# USB-C-UPDI.net
KiCad netlist of a schematic drawn in EAGLE
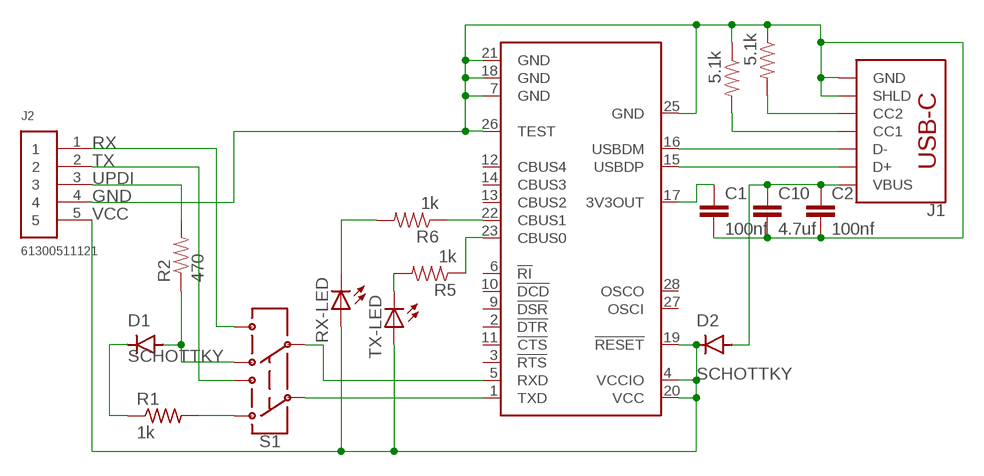
[diagram p0: schematic, sheet 1]

(export (version "E")
  (design (tool "Eeschema 10.0.6"))
  (components
    (comp (ref "C1")
      (value "100nf")
      (footprint "eagle-import:1206")
      (libsource (lib "eagle-import") (part "CAP1206"))
    )
    (comp (ref "C2")
      (value "100nf")
      (footprint "eagle-import:1206")
      (libsource (lib "eagle-import") (part "CAP1206"))
    )
    (comp (ref "C10")
      (value "4.7uf")
      (footprint "eagle-import:1206")
      (libsource (lib "eagle-import") (part "CAP1206"))
    )
    (comp (ref "D1")
      (value "SCHOTTKY")
      (footprint "eagle-import:MINI-SMA")
      (libsource (lib "eagle-import") (part "DIODE_SCHOTTKY_CDBM1100-G"))
    )
    (comp (ref "D2")
      (value "SCHOTTKY")
      (footprint "eagle-import:MINI-SMA")
      (libsource (lib "eagle-import") (part "DIODE_SCHOTTKY_CDBM1100-G"))
    )
    (comp (ref "IC1")
      (value "FT232RL")
      (footprint "eagle-import:SSOP28")
      (libsource (lib "eagle-import") (part "FT232RL"))
    )
    (comp (ref "J1")
      (value "USB_C_4-LAYER_PADS")
      (footprint "eagle-import:USB-C-16P_4LAYER-PADS")
      (libsource (lib "eagle-import") (part "USB_C_4-LAYER_PADS"))
    )
    (comp (ref "J2")
      (value "61300511121")
      (footprint "eagle-import:61300511121")
      (fields
        (field (name "DIGI_KEY_PART_NUMBER") "732-5318-ND")
        (field (name "MANUFACTURER") "Wurth Electronics Inc.")
        (field (name "CREATED_BY") "PCBLayout.com")
      )
      (libsource (lib "eagle-import") (part "61300511121"))
    )
    (comp (ref "R1")
      (value "1k")
      (footprint "eagle-import:R1206FAB")
      (libsource (lib "eagle-import") (part "R1206FAB"))
    )
    (comp (ref "R2")
      (value "470")
      (footprint "eagle-import:1206")
      (libsource (lib "eagle-import") (part "RESISTOR1206"))
    )
    (comp (ref "R5")
      (value "1k")
      (footprint "eagle-import:1206")
      (libsource (lib "eagle-import") (part "RESISTOR1206"))
    )
    (comp (ref "R6")
      (value "1k")
      (footprint "eagle-import:1206")
      (libsource (lib "eagle-import") (part "RESISTOR1206"))
    )
    (comp (ref "R9")
      (value "5.1k")
      (footprint "eagle-import:1206")
      (libsource (lib "eagle-import") (part "RESISTOR1206"))
    )
    (comp (ref "R10")
      (value "5.1k")
      (footprint "eagle-import:1206")
      (libsource (lib "eagle-import") (part "RESISTOR1206"))
    )
    (comp (ref "RX-LED")
      (value "LED")
      (footprint "eagle-import:LED1206")
      (libsource (lib "eagle-import") (part "LED"))
    )
    (comp (ref "S1")
      (value "SWITCH-DPDT-SMD-AYZ0202")
      (footprint "eagle-import:SWITCH_DPDT_SMD_AYZ0202")
      (libsource (lib "eagle-import") (part "SWITCH-DPDT-SMD-AYZ0202"))
    )
    (comp (ref "TX-LED")
      (value "LED")
      (footprint "eagle-import:LED1206")
      (libsource (lib "eagle-import") (part "LED"))
    )
  )
  (nets
    (net (code "1") (name "/GND") (class "Default")
      (node (ref "C1") (pin "2") (pinfunction "2_2") (pintype "passive"))
      (node (ref "C10") (pin "2") (pinfunction "2_2") (pintype "passive"))
      (node (ref "C2") (pin "2") (pinfunction "2_2") (pintype "passive"))
      (node (ref "IC1") (pin "18") (pinfunction "GND_18") (pintype "power_in"))
      (node (ref "IC1") (pin "21") (pinfunction "GND_21") (pintype "power_in"))
      (node (ref "IC1") (pin "25") (pinfunction "GND_25") (pintype "power_in"))
      (node (ref "IC1") (pin "26") (pinfunction "TEST_26") (pintype "input"))
      (node (ref "IC1") (pin "7") (pinfunction "GND_7") (pintype "power_in"))
      (node (ref "J1") (pin "GND") (pinfunction "GND_GND") (pintype "bidirectional"))
      (node (ref "J1") (pin "GND2") (pinfunction "GND_GND2") (pintype "bidirectional"))
      (node (ref "J1") (pin "SHLD1") (pinfunction "SHLD_SHLD1") (pintype "bidirectional"))
      (node (ref "J1") (pin "SHLD2") (pinfunction "SHLD_SHLD2") (pintype "bidirectional"))
      (node (ref "J1") (pin "SHLD3") (pinfunction "SHLD_SHLD3") (pintype "bidirectional"))
      (node (ref "J1") (pin "SHLD4") (pinfunction "SHLD_SHLD4") (pintype "bidirectional"))
      (node (ref "J2") (pin "4") (pinfunction "4_4") (pintype "passive"))
      (node (ref "R10") (pin "1") (pinfunction "1_1") (pintype "passive"))
      (node (ref "R9") (pin "1") (pinfunction "1_1") (pintype "passive"))
    )
    (net (code "2") (name "/RX") (class "Default")
      (node (ref "J2") (pin "1") (pinfunction "1_1") (pintype "passive"))
      (node (ref "S1") (pin "4") (pinfunction "4_4") (pintype "bidirectional"))
    )
    (net (code "3") (name "/TX") (class "Default")
      (node (ref "J2") (pin "2") (pinfunction "2_2") (pintype "passive"))
      (node (ref "S1") (pin "1") (pinfunction "1_1") (pintype "bidirectional"))
    )
    (net (code "4") (name "/UPDI") (class "Default")
      (node (ref "J2") (pin "3") (pinfunction "3_3") (pintype "passive"))
      (node (ref "R2") (pin "2") (pinfunction "2_2") (pintype "passive"))
    )
    (net (code "5") (name "/VCC") (class "Default")
      (node (ref "D2") (pin "KATHODE") (pinfunction "KATHODE_KATHODE") (pintype "bidirectional"))
      (node (ref "IC1") (pin "19") (pinfunction "~{RESET}_19") (pintype "input"))
      (node (ref "IC1") (pin "20") (pinfunction "VCC_20") (pintype "power_in"))
      (node (ref "IC1") (pin "4") (pinfunction "VCCIO_4") (pintype "power_in"))
      (node (ref "J2") (pin "5") (pinfunction "5_5") (pintype "passive"))
      (node (ref "RX-LED") (pin "1") (pinfunction "A_1") (pintype "passive"))
      (node (ref "TX-LED") (pin "1") (pinfunction "A_1") (pintype "passive"))
    )
    (net (code "6") (name "Net-(C10-Pad1)") (class "Default")
      (node (ref "C10") (pin "1") (pinfunction "1_1") (pintype "passive"))
      (node (ref "C2") (pin "1") (pinfunction "1_1") (pintype "passive"))
      (node (ref "D2") (pin "ANODE") (pinfunction "ANODE_ANODE") (pintype "bidirectional"))
      (node (ref "J1") (pin "VBUS1") (pinfunction "VBUS_VBUS1") (pintype "bidirectional"))
      (node (ref "J1") (pin "VBUS2") (pinfunction "VBUS_VBUS2") (pintype "bidirectional"))
    )
    (net (code "7") (name "Net-(D1-PadANODE)") (class "Default")
      (node (ref "D1") (pin "ANODE") (pinfunction "ANODE_ANODE") (pintype "bidirectional"))
      (node (ref "R2") (pin "1") (pinfunction "1_1") (pintype "passive"))
      (node (ref "S1") (pin "6") (pinfunction "6_6") (pintype "bidirectional"))
    )
    (net (code "8") (name "Net-(D1-PadKATHODE)") (class "Default")
      (node (ref "D1") (pin "KATHODE") (pinfunction "KATHODE_KATHODE") (pintype "bidirectional"))
      (node (ref "R1") (pin "1") (pinfunction "1_1") (pintype "passive"))
    )
    (net (code "9") (name "Net-(IC1-3V3OUT)") (class "Default")
      (node (ref "C1") (pin "1") (pinfunction "1_1") (pintype "passive"))
      (node (ref "IC1") (pin "17") (pinfunction "3V3OUT_17") (pintype "output"))
    )
    (net (code "10") (name "Net-(IC1-CBUS0)") (class "Default")
      (node (ref "IC1") (pin "23") (pinfunction "CBUS0_23") (pintype "bidirectional"))
      (node (ref "R5") (pin "1") (pinfunction "1_1") (pintype "passive"))
    )
    (net (code "11") (name "Net-(IC1-CBUS1)") (class "Default")
      (node (ref "IC1") (pin "22") (pinfunction "CBUS1_22") (pintype "bidirectional"))
      (node (ref "R6") (pin "1") (pinfunction "1_1") (pintype "passive"))
    )
    (net (code "12") (name "Net-(IC1-RXD)") (class "Default")
      (node (ref "IC1") (pin "5") (pinfunction "RXD_5") (pintype "input"))
      (node (ref "S1") (pin "5") (pinfunction "5_5") (pintype "bidirectional"))
    )
    (net (code "13") (name "Net-(IC1-TXD)") (class "Default")
      (node (ref "IC1") (pin "1") (pinfunction "TXD_1") (pintype "output"))
      (node (ref "S1") (pin "2") (pinfunction "2_2") (pintype "bidirectional"))
    )
    (net (code "14") (name "Net-(IC1-USBDM)") (class "Default")
      (node (ref "IC1") (pin "16") (pinfunction "USBDM_16") (pintype "bidirectional"))
      (node (ref "J1") (pin "A7") (pinfunction "D-_A7") (pintype "bidirectional"))
      (node (ref "J1") (pin "B7") (pinfunction "D-_B7") (pintype "bidirectional"))
    )
    (net (code "15") (name "Net-(IC1-USBDP)") (class "Default")
      (node (ref "IC1") (pin "15") (pinfunction "USBDP_15") (pintype "bidirectional"))
      (node (ref "J1") (pin "A6") (pinfunction "D+_A6") (pintype "bidirectional"))
      (node (ref "J1") (pin "B6") (pinfunction "D+_B6") (pintype "bidirectional"))
    )
    (net (code "16") (name "Net-(J1-CC1)") (class "Default")
      (node (ref "J1") (pin "A5") (pinfunction "CC1_A5") (pintype "bidirectional"))
      (node (ref "R9") (pin "2") (pinfunction "2_2") (pintype "passive"))
    )
    (net (code "17") (name "Net-(J1-CC2)") (class "Default")
      (node (ref "J1") (pin "B5") (pinfunction "CC2_B5") (pintype "bidirectional"))
      (node (ref "R10") (pin "2") (pinfunction "2_2") (pintype "passive"))
    )
    (net (code "18") (name "Net-(R1-Pad2)") (class "Default")
      (node (ref "R1") (pin "2") (pinfunction "2_2") (pintype "passive"))
      (node (ref "S1") (pin "3") (pinfunction "3_3") (pintype "bidirectional"))
    )
    (net (code "19") (name "Net-(RX-LED-C)") (class "Default")
      (node (ref "R6") (pin "2") (pinfunction "2_2") (pintype "passive"))
      (node (ref "RX-LED") (pin "2") (pinfunction "C_2") (pintype "passive"))
    )
    (net (code "20") (name "Net-(TX-LED-C)") (class "Default")
      (node (ref "R5") (pin "2") (pinfunction "2_2") (pintype "passive"))
      (node (ref "TX-LED") (pin "2") (pinfunction "C_2") (pintype "passive"))
    )
    (net (code "21") (name "unconnected-(IC1-CBUS2-Pad13)") (class "Default")
      (node (ref "IC1") (pin "13") (pinfunction "CBUS2_13") (pintype "bidirectional"))
    )
    (net (code "22") (name "unconnected-(IC1-CBUS3-Pad14)") (class "Default")
      (node (ref "IC1") (pin "14") (pinfunction "CBUS3_14") (pintype "bidirectional"))
    )
    (net (code "23") (name "unconnected-(IC1-CBUS4-Pad12)") (class "Default")
      (node (ref "IC1") (pin "12") (pinfunction "CBUS4_12") (pintype "bidirectional"))
    )
    (net (code "24") (name "unconnected-(IC1-OSCI-Pad27)") (class "Default")
      (node (ref "IC1") (pin "27") (pinfunction "OSCI_27") (pintype "input"))
    )
    (net (code "25") (name "unconnected-(IC1-OSCO-Pad28)") (class "Default")
      (node (ref "IC1") (pin "28") (pinfunction "OSCO_28") (pintype "output"))
    )
    (net (code "26") (name "unconnected-(IC1-~{CTS}-Pad11)") (class "Default")
      (node (ref "IC1") (pin "11") (pinfunction "~{CTS}_11") (pintype "input"))
    )
    (net (code "27") (name "unconnected-(IC1-~{DCD}-Pad10)") (class "Default")
      (node (ref "IC1") (pin "10") (pinfunction "~{DCD}_10") (pintype "input"))
    )
    (net (code "28") (name "unconnected-(IC1-~{DSR}-Pad9)") (class "Default")
      (node (ref "IC1") (pin "9") (pinfunction "~{DSR}_9") (pintype "input"))
    )
    (net (code "29") (name "unconnected-(IC1-~{DTR}-Pad2)") (class "Default")
      (node (ref "IC1") (pin "2") (pinfunction "~{DTR}_2") (pintype "output"))
    )
    (net (code "30") (name "unconnected-(IC1-~{RI}-Pad6)") (class "Default")
      (node (ref "IC1") (pin "6") (pinfunction "~{RI}_6") (pintype "input"))
    )
    (net (code "31") (name "unconnected-(IC1-~{RTS}-Pad3)") (class "Default")
      (node (ref "IC1") (pin "3") (pinfunction "~{RTS}_3") (pintype "output"))
    )
  )
)
